# FAT42.net
KiCad netlist of a schematic drawn in Altium Designer
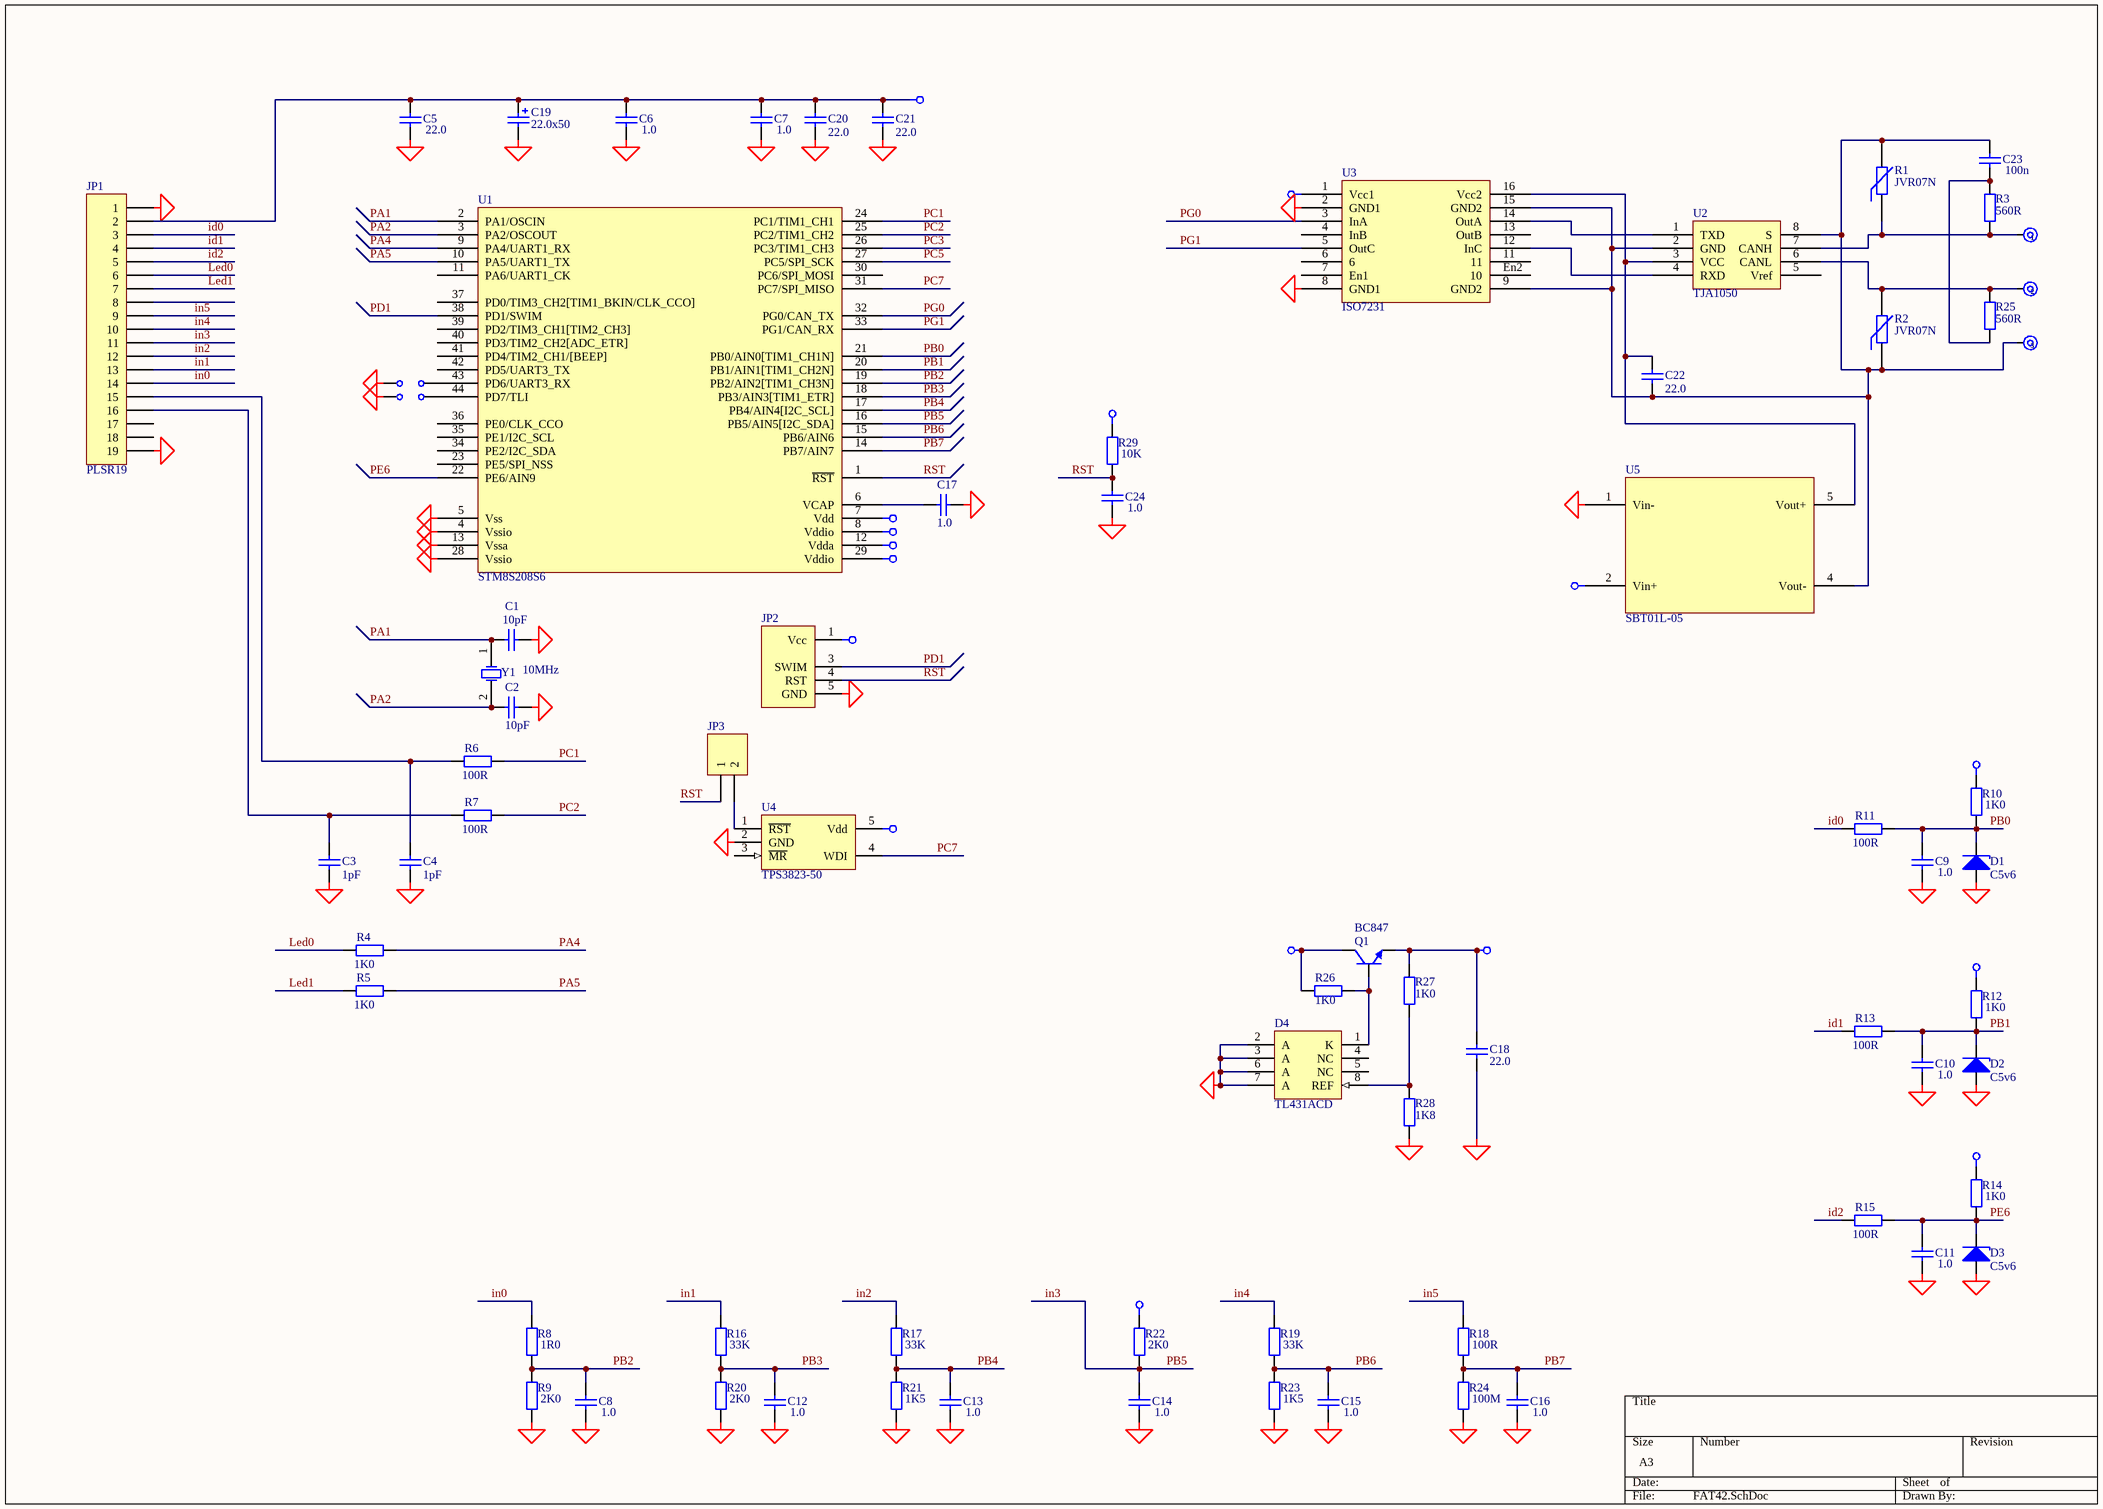
[diagram p0: FAT42.SchDoc]

(export (version "E")
  (design (tool "Eeschema 10.0.6"))
  (components
    (comp (ref "1")
      (value "~")
      (footprint "PIN2R")
      (description "Socket")
      (fields (field (name "MANUFACTURER") "Generic Components") (field (name "PUBLISHER") "Altium Limited"))
      (libsource (lib "PAL") (part "Socket_Ring"))
    )
    (comp (ref "2")
      (value "~")
      (footprint "PIN2R")
      (description "Socket")
      (fields (field (name "MANUFACTURER") "Generic Components") (field (name "PUBLISHER") "Altium Limited"))
      (libsource (lib "PAL") (part "Socket_Ring"))
    )
    (comp (ref "3")
      (value "~")
      (footprint "PIN2R")
      (description "Socket")
      (fields (field (name "MANUFACTURER") "Generic Components") (field (name "PUBLISHER") "Altium Limited"))
      (libsource (lib "PAL") (part "Socket_Ring"))
    )
    (comp (ref "C1")
      (value "10pF")
      (footprint "_1206")
      (description "Capacitor (Semiconductor SIM Model)")
      (fields (field (name "MANUFACTURER") "Generic Components") (field (name "PUBLISHER") "Altium Limited"))
      (libsource (lib "Miscellaneous Devices") (part "Cap Semi"))
    )
    (comp (ref "C2")
      (value "10pF")
      (footprint "_1206")
      (description "Capacitor (Semiconductor SIM Model)")
      (fields (field (name "MANUFACTURER") "Generic Components") (field (name "PUBLISHER") "Altium Limited"))
      (libsource (lib "Miscellaneous Devices") (part "Cap Semi"))
    )
    (comp (ref "C3")
      (value "1pF")
      (footprint "_1206")
      (description "Capacitor (Semiconductor SIM Model)")
      (fields (field (name "MANUFACTURER") "Generic Components") (field (name "PUBLISHER") "Altium Limited"))
      (libsource (lib "Miscellaneous Devices") (part "Cap Semi"))
    )
    (comp (ref "C4")
      (value "1pF")
      (footprint "_1206")
      (description "Capacitor (Semiconductor SIM Model)")
      (fields (field (name "MANUFACTURER") "Generic Components") (field (name "PUBLISHER") "Altium Limited"))
      (libsource (lib "Miscellaneous Devices") (part "Cap Semi"))
    )
    (comp (ref "C5")
      (value "22.0")
      (footprint "_1206")
      (description "Capacitor (Semiconductor SIM Model)")
      (fields (field (name "MANUFACTURER") "Generic Components") (field (name "PUBLISHER") "Altium Limited"))
      (libsource (lib "Miscellaneous Devices") (part "Cap Semi"))
    )
    (comp (ref "C6")
      (value "1.0")
      (footprint "_1206")
      (description "Capacitor (Semiconductor SIM Model)")
      (fields (field (name "MANUFACTURER") "Generic Components") (field (name "PUBLISHER") "Altium Limited"))
      (libsource (lib "Miscellaneous Devices") (part "Cap Semi"))
    )
    (comp (ref "C7")
      (value "1.0")
      (footprint "_1206")
      (description "Capacitor (Semiconductor SIM Model)")
      (fields (field (name "MANUFACTURER") "Generic Components") (field (name "PUBLISHER") "Altium Limited"))
      (libsource (lib "Miscellaneous Devices") (part "Cap Semi"))
    )
    (comp (ref "C8")
      (value "1.0")
      (footprint "_1206")
      (description "Capacitor (Semiconductor SIM Model)")
      (fields (field (name "MANUFACTURER") "Generic Components") (field (name "PUBLISHER") "Altium Limited"))
      (libsource (lib "Miscellaneous Devices") (part "Cap Semi"))
    )
    (comp (ref "C9")
      (value "1.0")
      (footprint "_1206")
      (description "Capacitor (Semiconductor SIM Model)")
      (fields (field (name "MANUFACTURER") "Generic Components") (field (name "PUBLISHER") "Altium Limited"))
      (libsource (lib "Miscellaneous Devices") (part "Cap Semi"))
    )
    (comp (ref "C10")
      (value "1.0")
      (footprint "_1206")
      (description "Capacitor (Semiconductor SIM Model)")
      (fields (field (name "MANUFACTURER") "Generic Components") (field (name "PUBLISHER") "Altium Limited"))
      (libsource (lib "Miscellaneous Devices") (part "Cap Semi"))
    )
    (comp (ref "C11")
      (value "1.0")
      (footprint "_1206")
      (description "Capacitor (Semiconductor SIM Model)")
      (fields (field (name "MANUFACTURER") "Generic Components") (field (name "PUBLISHER") "Altium Limited"))
      (libsource (lib "Miscellaneous Devices") (part "Cap Semi"))
    )
    (comp (ref "C12")
      (value "1.0")
      (footprint "_1206")
      (description "Capacitor (Semiconductor SIM Model)")
      (fields (field (name "MANUFACTURER") "Generic Components") (field (name "PUBLISHER") "Altium Limited"))
      (libsource (lib "Miscellaneous Devices") (part "Cap Semi"))
    )
    (comp (ref "C13")
      (value "1.0")
      (footprint "_1206")
      (description "Capacitor (Semiconductor SIM Model)")
      (fields (field (name "MANUFACTURER") "Generic Components") (field (name "PUBLISHER") "Altium Limited"))
      (libsource (lib "Miscellaneous Devices") (part "Cap Semi"))
    )
    (comp (ref "C14")
      (value "1.0")
      (footprint "_1206")
      (description "Capacitor (Semiconductor SIM Model)")
      (fields (field (name "MANUFACTURER") "Generic Components") (field (name "PUBLISHER") "Altium Limited"))
      (libsource (lib "Miscellaneous Devices") (part "Cap Semi"))
    )
    (comp (ref "C15")
      (value "1.0")
      (footprint "_1206")
      (description "Capacitor (Semiconductor SIM Model)")
      (fields (field (name "MANUFACTURER") "Generic Components") (field (name "PUBLISHER") "Altium Limited"))
      (libsource (lib "Miscellaneous Devices") (part "Cap Semi"))
    )
    (comp (ref "C16")
      (value "1.0")
      (footprint "_1206")
      (description "Capacitor (Semiconductor SIM Model)")
      (fields (field (name "MANUFACTURER") "Generic Components") (field (name "PUBLISHER") "Altium Limited"))
      (libsource (lib "Miscellaneous Devices") (part "Cap Semi"))
    )
    (comp (ref "C17")
      (value "1.0")
      (footprint "_1206")
      (description "Capacitor (Semiconductor SIM Model)")
      (fields (field (name "MANUFACTURER") "Generic Components") (field (name "PUBLISHER") "Altium Limited"))
      (libsource (lib "Miscellaneous Devices") (part "Cap Semi"))
    )
    (comp (ref "C18")
      (value "22.0")
      (footprint "_1206")
      (description "Capacitor (Semiconductor SIM Model)")
      (fields (field (name "MANUFACTURER") "Generic Components") (field (name "PUBLISHER") "Altium Limited"))
      (libsource (lib "Miscellaneous Devices") (part "Cap Semi"))
    )
    (comp (ref "C19")
      (value "22.0x50")
      (footprint "el3")
      (description "Polarized Capacitor (Radial)")
      (fields (field (name "MANUFACTURER") "Generic Components") (field (name "PUBLISHER") "Altium Limited"))
      (libsource (lib "PAL") (part "Cap Pol1"))
    )
    (comp (ref "C20")
      (value "22.0")
      (footprint "_1206")
      (description "Capacitor (Semiconductor SIM Model)")
      (fields (field (name "MANUFACTURER") "Generic Components") (field (name "PUBLISHER") "Altium Limited"))
      (libsource (lib "Miscellaneous Devices") (part "Cap Semi"))
    )
    (comp (ref "C21")
      (value "22.0")
      (footprint "_1206")
      (description "Capacitor (Semiconductor SIM Model)")
      (fields (field (name "MANUFACTURER") "Generic Components") (field (name "PUBLISHER") "Altium Limited"))
      (libsource (lib "Miscellaneous Devices") (part "Cap Semi"))
    )
    (comp (ref "C22")
      (value "22.0")
      (footprint "_1206")
      (description "Capacitor (Semiconductor SIM Model)")
      (fields (field (name "MANUFACTURER") "Generic Components") (field (name "PUBLISHER") "Altium Limited"))
      (libsource (lib "Miscellaneous Devices") (part "Cap Semi"))
    )
    (comp (ref "C23")
      (value "100n")
      (footprint "_1206")
      (description "Capacitor (Semiconductor SIM Model)")
      (fields (field (name "MANUFACTURER") "Generic Components") (field (name "PUBLISHER") "Altium Limited"))
      (libsource (lib "Miscellaneous Devices") (part "Cap Semi"))
    )
    (comp (ref "C24")
      (value "1.0")
      (footprint "_1206")
      (description "Capacitor (Semiconductor SIM Model)")
      (fields (field (name "MANUFACTURER") "Generic Components") (field (name "PUBLISHER") "Altium Limited"))
      (libsource (lib "Miscellaneous Devices") (part "Cap Semi"))
    )
    (comp (ref "D1")
      (value "C5v6")
      (footprint "_1206d")
      (description "Default Diode")
      (fields (field (name "MANUFACTURER") "Generic Components") (field (name "PUBLISHER") "Altium Limited"))
      (libsource (lib "PAL") (part "Zener"))
    )
    (comp (ref "D2")
      (value "C5v6")
      (footprint "_1206d")
      (description "Default Diode")
      (fields (field (name "MANUFACTURER") "Generic Components") (field (name "PUBLISHER") "Altium Limited"))
      (libsource (lib "PAL") (part "Zener"))
    )
    (comp (ref "D3")
      (value "C5v6")
      (footprint "_1206d")
      (description "Default Diode")
      (fields (field (name "MANUFACTURER") "Generic Components") (field (name "PUBLISHER") "Altium Limited"))
      (libsource (lib "PAL") (part "Zener"))
    )
    (comp (ref "D4")
      (value "TL431ACD")
      (footprint "SO-G8")
      (description "Programmable Precision Reference")
      (fields (field (name "MANUFACTURER") "Motorola") (field (name "PUBLISHER") "Altium Limited"))
      (libsource (lib "Motorola Power Management Voltage Reference") (part "TL431ACD"))
    )
    (comp (ref "J1")
      (value "~")
      (footprint "jmp")
      (description "Switch")
      (fields (field (name "MANUFACTURER") "Generic Components") (field (name "PUBLISHER") "Altium Limited"))
      (libsource (lib "PAL") (part "JMP"))
    )
    (comp (ref "J2")
      (value "~")
      (footprint "jmp")
      (description "Switch")
      (fields (field (name "MANUFACTURER") "Generic Components") (field (name "PUBLISHER") "Altium Limited"))
      (libsource (lib "PAL") (part "JMP"))
    )
    (comp (ref "JP1")
      (value "PLSR19")
      (footprint "HDR1X19")
      (description "Header, 19-Pin")
      (fields (field (name "MANUFACTURER") "Generic Components") (field (name "PUBLISHER") "Altium Limited"))
      (libsource (lib "Miscellaneous Connectors") (part "Header 19"))
    )
    (comp (ref "JP2") (value "~") (footprint "HDR1X5_uart") (libsource (lib "PAL") (part "SWIM_CONN")))
    (comp (ref "JP3")
      (value "PLS2")
      (footprint "HDR1X2")
      (description "Header, 2-Pin")
      (fields (field (name "MANUFACTURER") "Generic Components") (field (name "PUBLISHER") "Altium Limited"))
      (libsource (lib "Miscellaneous Connectors") (part "Header 2"))
    )
    (comp (ref "Q1")
      (value "BC847")
      (footprint "SO-G3")
      (description "General Purpose Transistor NPN Silicon")
      (fields (field (name "MANUFACTURER") "Motorola") (field (name "PUBLISHER") "Altium Limited"))
      (libsource (lib "PAL") (part "BC847ALT1"))
    )
    (comp (ref "R1")
      (value "JVR07N")
      (footprint "JVR07N")
      (description "Varistor (Voltage-Sensitive Resistor)")
      (fields (field (name "MANUFACTURER") "Generic Components") (field (name "PUBLISHER") "Altium Limited"))
      (libsource (lib "Miscellaneous Devices") (part "Res Varistor"))
    )
    (comp (ref "R2")
      (value "JVR07N")
      (footprint "JVR07N")
      (description "Varistor (Voltage-Sensitive Resistor)")
      (fields (field (name "MANUFACTURER") "Generic Components") (field (name "PUBLISHER") "Altium Limited"))
      (libsource (lib "Miscellaneous Devices") (part "Res Varistor"))
    )
    (comp (ref "R3")
      (value "560R")
      (footprint "_1206")
      (description "Resistor")
      (fields (field (name "MANUFACTURER") "Generic Components") (field (name "PUBLISHER") "Altium Limited"))
      (libsource (lib "") (part "Res2_1"))
    )
    (comp (ref "R4")
      (value "1K0")
      (footprint "_1206")
      (description "Resistor")
      (fields (field (name "MANUFACTURER") "Generic Components") (field (name "PUBLISHER") "Altium Limited"))
      (libsource (lib "") (part "Res2_1"))
    )
    (comp (ref "R5")
      (value "1K0")
      (footprint "_1206")
      (description "Resistor")
      (fields (field (name "MANUFACTURER") "Generic Components") (field (name "PUBLISHER") "Altium Limited"))
      (libsource (lib "") (part "Res2_1"))
    )
    (comp (ref "R6")
      (value "100R")
      (footprint "_1206")
      (description "Resistor")
      (fields (field (name "MANUFACTURER") "Generic Components") (field (name "PUBLISHER") "Altium Limited"))
      (libsource (lib "Miscellaneous Devices") (part "Res2"))
    )
    (comp (ref "R7")
      (value "100R")
      (footprint "_1206")
      (description "Resistor")
      (fields (field (name "MANUFACTURER") "Generic Components") (field (name "PUBLISHER") "Altium Limited"))
      (libsource (lib "Miscellaneous Devices") (part "Res2"))
    )
    (comp (ref "R8")
      (value "1R0")
      (footprint "_1206")
      (description "Resistor")
      (fields (field (name "MANUFACTURER") "Generic Components") (field (name "PUBLISHER") "Altium Limited"))
      (libsource (lib "") (part "Res2_2"))
    )
    (comp (ref "R9")
      (value "2K0")
      (footprint "_1206")
      (description "Resistor")
      (fields (field (name "MANUFACTURER") "Generic Components") (field (name "PUBLISHER") "Altium Limited"))
      (libsource (lib "") (part "Res2_2"))
    )
    (comp (ref "R10")
      (value "1K0")
      (footprint "_1206")
      (description "Resistor")
      (fields (field (name "MANUFACTURER") "Generic Components") (field (name "PUBLISHER") "Altium Limited"))
      (libsource (lib "") (part "Res2_3"))
    )
    (comp (ref "R11")
      (value "100R")
      (footprint "_1206")
      (description "Resistor")
      (fields (field (name "MANUFACTURER") "Generic Components") (field (name "PUBLISHER") "Altium Limited"))
      (libsource (lib "Miscellaneous Devices") (part "Res2"))
    )
    (comp (ref "R12")
      (value "1K0")
      (footprint "_1206")
      (description "Resistor")
      (fields (field (name "MANUFACTURER") "Generic Components") (field (name "PUBLISHER") "Altium Limited"))
      (libsource (lib "") (part "Res2_3"))
    )
    (comp (ref "R13")
      (value "100R")
      (footprint "_1206")
      (description "Resistor")
      (fields (field (name "MANUFACTURER") "Generic Components") (field (name "PUBLISHER") "Altium Limited"))
      (libsource (lib "Miscellaneous Devices") (part "Res2"))
    )
    (comp (ref "R14")
      (value "1K0")
      (footprint "_1206")
      (description "Resistor")
      (fields (field (name "MANUFACTURER") "Generic Components") (field (name "PUBLISHER") "Altium Limited"))
      (libsource (lib "") (part "Res2_3"))
    )
    (comp (ref "R15")
      (value "100R")
      (footprint "_1206")
      (description "Resistor")
      (fields (field (name "MANUFACTURER") "Generic Components") (field (name "PUBLISHER") "Altium Limited"))
      (libsource (lib "Miscellaneous Devices") (part "Res2"))
    )
    (comp (ref "R16")
      (value "33K")
      (footprint "_1206")
      (description "Resistor")
      (fields (field (name "MANUFACTURER") "Generic Components") (field (name "PUBLISHER") "Altium Limited"))
      (libsource (lib "") (part "Res2_2"))
    )
    (comp (ref "R17")
      (value "33K")
      (footprint "_1206")
      (description "Resistor")
      (fields (field (name "MANUFACTURER") "Generic Components") (field (name "PUBLISHER") "Altium Limited"))
      (libsource (lib "") (part "Res2_2"))
    )
    (comp (ref "R18")
      (value "100R")
      (footprint "_1206")
      (description "Resistor")
      (fields (field (name "MANUFACTURER") "Generic Components") (field (name "PUBLISHER") "Altium Limited"))
      (libsource (lib "") (part "Res2_2"))
    )
    (comp (ref "R19")
      (value "33K")
      (footprint "_1206")
      (description "Resistor")
      (fields (field (name "MANUFACTURER") "Generic Components") (field (name "PUBLISHER") "Altium Limited"))
      (libsource (lib "") (part "Res2_2"))
    )
    (comp (ref "R20")
      (value "2K0")
      (footprint "_1206")
      (description "Resistor")
      (fields (field (name "MANUFACTURER") "Generic Components") (field (name "PUBLISHER") "Altium Limited"))
      (libsource (lib "") (part "Res2_2"))
    )
    (comp (ref "R21")
      (value "1K5")
      (footprint "_1206")
      (description "Resistor")
      (fields (field (name "MANUFACTURER") "Generic Components") (field (name "PUBLISHER") "Altium Limited"))
      (libsource (lib "") (part "Res2_2"))
    )
    (comp (ref "R22")
      (value "2K0")
      (footprint "_1206")
      (description "Resistor")
      (fields (field (name "MANUFACTURER") "Generic Components") (field (name "PUBLISHER") "Altium Limited"))
      (libsource (lib "") (part "Res2_2"))
    )
    (comp (ref "R23")
      (value "1K5")
      (footprint "_1206")
      (description "Resistor")
      (fields (field (name "MANUFACTURER") "Generic Components") (field (name "PUBLISHER") "Altium Limited"))
      (libsource (lib "") (part "Res2_2"))
    )
    (comp (ref "R24")
      (value "100M")
      (footprint "_1206")
      (description "Resistor")
      (fields (field (name "MANUFACTURER") "Generic Components") (field (name "PUBLISHER") "Altium Limited"))
      (libsource (lib "") (part "Res2_2"))
    )
    (comp (ref "R25")
      (value "560R")
      (footprint "_1206")
      (description "Resistor")
      (fields (field (name "MANUFACTURER") "Generic Components") (field (name "PUBLISHER") "Altium Limited"))
      (libsource (lib "") (part "Res2_1"))
    )
    (comp (ref "R26")
      (value "1K0")
      (footprint "_1206")
      (description "Resistor")
      (fields (field (name "MANUFACTURER") "Generic Components") (field (name "PUBLISHER") "Altium Limited"))
      (libsource (lib "") (part "Res2_4"))
    )
    (comp (ref "R27")
      (value "1K0")
      (footprint "_1206")
      (description "Resistor")
      (fields (field (name "MANUFACTURER") "Generic Components") (field (name "PUBLISHER") "Altium Limited"))
      (libsource (lib "") (part "Res2_1"))
    )
    (comp (ref "R28")
      (value "1K8")
      (footprint "_1206")
      (description "Resistor")
      (fields (field (name "MANUFACTURER") "Generic Components") (field (name "PUBLISHER") "Altium Limited"))
      (libsource (lib "") (part "Res2_1"))
    )
    (comp (ref "R29")
      (value "10K")
      (footprint "_1206")
      (description "Resistor")
      (fields (field (name "MANUFACTURER") "Generic Components") (field (name "PUBLISHER") "Altium Limited"))
      (libsource (lib "") (part "Res2_3"))
    )
    (comp (ref "U1")
      (value "STM8S208S6")
      (footprint "QFP10X10-G44/G10N")
      (libsource (lib "PAL") (part "STM8S208S6"))
    )
    (comp (ref "U2") (value "TJA1050") (footprint "SO-G8/D5") (libsource (lib "PAL") (part "TJA1050")))
    (comp (ref "U3") (value "ISO7231") (footprint "SO-G16/D10.4") (libsource (lib "PAL") (part "ISO7231")))
    (comp (ref "U4")
      (value "TPS3823-50")
      (footprint "SO-G5/P.95")
      (description "Reset IC")
      (fields
        (field (name "MANUFACTURER") "National Semiconductor")
        (field (name "PUBLISHER") "Altium Limited")
      )
      (libsource (lib "PAL") (part "TPS3823"))
    )
    (comp (ref "U5") (value "SBT01L-05") (footprint "SBT01DET01") (libsource (lib "PAL") (part "SBT01L")))
    (comp (ref "Y1")
      (value "10MHz")
      (footprint "QWARZ1")
      (description "Crystal Oscillator")
      (fields (field (name "MANUFACTURER") "Generic Components") (field (name "PUBLISHER") "Altium Limited"))
      (libsource (lib "Miscellaneous Devices") (part "XTAL"))
    )
  )
  (nets
    (net (code "1") (name "+5v") (class "Default")
      (node (ref "C19") (pin "1") (pinfunction "1_1") (pintype "passive"))
      (node (ref "C20") (pin "1") (pinfunction "1_1") (pintype "passive"))
      (node (ref "C21") (pin "1") (pinfunction "1_1") (pintype "passive"))
      (node (ref "C5") (pin "2") (pinfunction "2_2") (pintype "passive"))
      (node (ref "C6") (pin "2") (pinfunction "2_2") (pintype "passive"))
      (node (ref "C7") (pin "2") (pinfunction "2_2") (pintype "passive"))
      (node (ref "JP1") (pin "2") (pinfunction "2_2") (pintype "passive"))
      (node (ref "JP2") (pin "1") (pinfunction "Vcc_1") (pintype "passive"))
      (node (ref "Q1") (pin "3") (pinfunction "C_3") (pintype "passive"))
      (node (ref "R10") (pin "1") (pinfunction "1_1") (pintype "passive"))
      (node (ref "R12") (pin "1") (pinfunction "1_1") (pintype "passive"))
      (node (ref "R14") (pin "1") (pinfunction "1_1") (pintype "passive"))
      (node (ref "R22") (pin "2") (pinfunction "2_2") (pintype "passive"))
      (node (ref "R26") (pin "1") (pinfunction "1_1") (pintype "passive"))
      (node (ref "R29") (pin "1") (pinfunction "1_1") (pintype "passive"))
      (node (ref "U1") (pin "29") (pinfunction "Vddio_29") (pintype "passive"))
      (node (ref "U1") (pin "7") (pinfunction "Vdd_7") (pintype "passive"))
      (node (ref "U1") (pin "8") (pinfunction "Vddio_8") (pintype "passive"))
      (node (ref "U3") (pin "1") (pinfunction "Vcc1_1") (pintype "passive"))
      (node (ref "U4") (pin "5") (pinfunction "Vdd_5") (pintype "power_in"))
      (node (ref "U5") (pin "2") (pinfunction "Vin+_2") (pintype "passive"))
    )
    (net (code "2") (name "/Led0") (class "Default")
      (node (ref "JP1") (pin "6") (pinfunction "6_6") (pintype "passive"))
      (node (ref "R4") (pin "1") (pinfunction "1_1") (pintype "passive"))
    )
    (net (code "3") (name "/Led1") (class "Default")
      (node (ref "JP1") (pin "7") (pinfunction "7_7") (pintype "passive"))
      (node (ref "R5") (pin "1") (pinfunction "1_1") (pintype "passive"))
    )
    (net (code "4") (name "/PA1") (class "Default")
      (node (ref "C1") (pin "2") (pinfunction "2_2") (pintype "passive"))
      (node (ref "U1") (pin "2") (pinfunction "PA1/OSCIN_2") (pintype "passive"))
      (node (ref "Y1") (pin "1") (pinfunction "OSC1_1") (pintype "passive"))
    )
    (net (code "5") (name "/PA2") (class "Default")
      (node (ref "C2") (pin "2") (pinfunction "2_2") (pintype "passive"))
      (node (ref "U1") (pin "3") (pinfunction "PA2/OSCOUT_3") (pintype "passive"))
      (node (ref "Y1") (pin "2") (pinfunction "OSC2_2") (pintype "passive"))
    )
    (net (code "6") (name "/PA4") (class "Default")
      (node (ref "R4") (pin "2") (pinfunction "2_2") (pintype "passive"))
      (node (ref "U1") (pin "9") (pinfunction "PA4/UART1_RX_9") (pintype "passive"))
    )
    (net (code "7") (name "/PA5") (class "Default")
      (node (ref "R5") (pin "2") (pinfunction "2_2") (pintype "passive"))
      (node (ref "U1") (pin "10") (pinfunction "PA5/UART1_TX_10") (pintype "passive"))
    )
    (net (code "8") (name "/PB0") (class "Default")
      (node (ref "C9") (pin "2") (pinfunction "2_2") (pintype "passive"))
      (node (ref "D1") (pin "2") (pinfunction "K_2") (pintype "passive"))
      (node (ref "R10") (pin "2") (pinfunction "2_2") (pintype "passive"))
      (node (ref "R11") (pin "1") (pinfunction "1_1") (pintype "passive"))
      (node (ref "U1") (pin "21") (pinfunction "PB0/AIN0[TIM1_CH1N]_21") (pintype "passive"))
    )
    (net (code "9") (name "/PB1") (class "Default")
      (node (ref "C10") (pin "2") (pinfunction "2_2") (pintype "passive"))
      (node (ref "D2") (pin "2") (pinfunction "K_2") (pintype "passive"))
      (node (ref "R12") (pin "2") (pinfunction "2_2") (pintype "passive"))
      (node (ref "R13") (pin "1") (pinfunction "1_1") (pintype "passive"))
      (node (ref "U1") (pin "20") (pinfunction "PB1/AIN1[TIM1_CH2N]_20") (pintype "passive"))
    )
    (net (code "10") (name "/PB2") (class "Default")
      (node (ref "C8") (pin "2") (pinfunction "2_2") (pintype "passive"))
      (node (ref "R8") (pin "1") (pinfunction "1_1") (pintype "passive"))
      (node (ref "R9") (pin "2") (pinfunction "2_2") (pintype "passive"))
      (node (ref "U1") (pin "19") (pinfunction "PB2/AIN2[TIM1_CH3N]_19") (pintype "passive"))
    )
    (net (code "11") (name "/PB3") (class "Default")
      (node (ref "C12") (pin "2") (pinfunction "2_2") (pintype "passive"))
      (node (ref "R16") (pin "1") (pinfunction "1_1") (pintype "passive"))
      (node (ref "R20") (pin "2") (pinfunction "2_2") (pintype "passive"))
      (node (ref "U1") (pin "18") (pinfunction "PB3/AIN3[TIM1_ETR]_18") (pintype "passive"))
    )
    (net (code "12") (name "/PB4") (class "Default")
      (node (ref "C13") (pin "2") (pinfunction "2_2") (pintype "passive"))
      (node (ref "R17") (pin "1") (pinfunction "1_1") (pintype "passive"))
      (node (ref "R21") (pin "2") (pinfunction "2_2") (pintype "passive"))
      (node (ref "U1") (pin "17") (pinfunction "PB4/AIN4[I2C_SCL]_17") (pintype "passive"))
    )
    (net (code "13") (name "/PB5") (class "Default")
      (node (ref "C14") (pin "2") (pinfunction "2_2") (pintype "passive"))
      (node (ref "JP1") (pin "11") (pinfunction "11_11") (pintype "passive"))
      (node (ref "R22") (pin "1") (pinfunction "1_1") (pintype "passive"))
      (node (ref "U1") (pin "16") (pinfunction "PB5/AIN5[I2C_SDA]_16") (pintype "passive"))
    )
    (net (code "14") (name "/PB6") (class "Default")
      (node (ref "C15") (pin "2") (pinfunction "2_2") (pintype "passive"))
      (node (ref "R19") (pin "1") (pinfunction "1_1") (pintype "passive"))
      (node (ref "R23") (pin "2") (pinfunction "2_2") (pintype "passive"))
      (node (ref "U1") (pin "15") (pinfunction "PB6/AIN6_15") (pintype "passive"))
    )
    (net (code "15") (name "/PB7") (class "Default")
      (node (ref "C16") (pin "2") (pinfunction "2_2") (pintype "passive"))
      (node (ref "R18") (pin "1") (pinfunction "1_1") (pintype "passive"))
      (node (ref "R24") (pin "2") (pinfunction "2_2") (pintype "passive"))
      (node (ref "U1") (pin "14") (pinfunction "PB7/AIN7_14") (pintype "passive"))
    )
    (net (code "16") (name "/PC1") (class "Default")
      (node (ref "R6") (pin "1") (pinfunction "1_1") (pintype "passive"))
      (node (ref "U1") (pin "24") (pinfunction "PC1/TIM1_CH1_24") (pintype "passive"))
    )
    (net (code "17") (name "/PC2") (class "Default")
      (node (ref "R7") (pin "1") (pinfunction "1_1") (pintype "passive"))
      (node (ref "U1") (pin "25") (pinfunction "PC2/TIM1_CH2_25") (pintype "passive"))
    )
    (net (code "18") (name "/PC3") (class "Default")
      (node (ref "U1") (pin "26") (pinfunction "PC3/TIM1_CH3_26") (pintype "passive"))
    )
    (net (code "19") (name "/PC5") (class "Default")
      (node (ref "U1") (pin "27") (pinfunction "PC5/SPI_SCK_27") (pintype "passive"))
    )
    (net (code "20") (name "/PC7") (class "Default")
      (node (ref "U1") (pin "31") (pinfunction "PC7/SPI_MISO_31") (pintype "passive"))
      (node (ref "U4") (pin "4") (pinfunction "WDI_4") (pintype "passive"))
    )
    (net (code "21") (name "/PD1") (class "Default")
      (node (ref "JP2") (pin "3") (pinfunction "SWIM_3") (pintype "passive"))
      (node (ref "U1") (pin "38") (pinfunction "PD1/SWIM_38") (pintype "passive"))
    )
    (net (code "22") (name "/PE6") (class "Default")
      (node (ref "C11") (pin "2") (pinfunction "2_2") (pintype "passive"))
      (node (ref "D3") (pin "2") (pinfunction "K_2") (pintype "passive"))
      (node (ref "R14") (pin "2") (pinfunction "2_2") (pintype "passive"))
      (node (ref "R15") (pin "1") (pinfunction "1_1") (pintype "passive"))
      (node (ref "U1") (pin "22") (pinfunction "PE6/AIN9_22") (pintype "passive"))
    )
    (net (code "23") (name "/PG0") (class "Default")
      (node (ref "U1") (pin "32") (pinfunction "PG0/CAN_TX_32") (pintype "passive"))
      (node (ref "U3") (pin "3") (pinfunction "InA_3") (pintype "passive"))
    )
    (net (code "24") (name "/PG1") (class "Default")
      (node (ref "U1") (pin "33") (pinfunction "PG1/CAN_RX_33") (pintype "passive"))
      (node (ref "U3") (pin "5") (pinfunction "OutC_5") (pintype "passive"))
    )
    (net (code "25") (name "/RST") (class "Default")
      (node (ref "C24") (pin "2") (pinfunction "2_2") (pintype "passive"))
      (node (ref "JP2") (pin "4") (pinfunction "RST_4") (pintype "passive"))
      (node (ref "JP3") (pin "1") (pinfunction "1_1") (pintype "passive"))
      (node (ref "R29") (pin "2") (pinfunction "2_2") (pintype "passive"))
      (node (ref "U1") (pin "1") (pinfunction "~{RST}_1") (pintype "passive"))
    )
    (net (code "26") (name "/id0") (class "Default")
      (node (ref "JP1") (pin "3") (pinfunction "3_3") (pintype "passive"))
      (node (ref "R11") (pin "2") (pinfunction "2_2") (pintype "passive"))
    )
    (net (code "27") (name "/id1") (class "Default")
      (node (ref "JP1") (pin "4") (pinfunction "4_4") (pintype "passive"))
      (node (ref "R13") (pin "2") (pinfunction "2_2") (pintype "passive"))
    )
    (net (code "28") (name "/id2") (class "Default")
      (node (ref "JP1") (pin "5") (pinfunction "5_5") (pintype "passive"))
      (node (ref "R15") (pin "2") (pinfunction "2_2") (pintype "passive"))
    )
    (net (code "29") (name "/in0") (class "Default")
      (node (ref "JP1") (pin "14") (pinfunction "14_14") (pintype "passive"))
      (node (ref "R8") (pin "2") (pinfunction "2_2") (pintype "passive"))
    )
    (net (code "30") (name "/in1") (class "Default")
      (node (ref "JP1") (pin "13") (pinfunction "13_13") (pintype "passive"))
      (node (ref "R16") (pin "2") (pinfunction "2_2") (pintype "passive"))
    )
    (net (code "31") (name "/in2") (class "Default")
      (node (ref "JP1") (pin "12") (pinfunction "12_12") (pintype "passive"))
      (node (ref "R17") (pin "2") (pinfunction "2_2") (pintype "passive"))
    )
    (net (code "32") (name "/in4") (class "Default")
      (node (ref "JP1") (pin "10") (pinfunction "10_10") (pintype "passive"))
      (node (ref "R19") (pin "2") (pinfunction "2_2") (pintype "passive"))
    )
    (net (code "33") (name "/in5") (class "Default")
      (node (ref "JP1") (pin "9") (pinfunction "9_9") (pintype "passive"))
      (node (ref "R18") (pin "2") (pinfunction "2_2") (pintype "passive"))
    )
    (net (code "34") (name "GND") (class "Default")
      (node (ref "C1") (pin "1") (pinfunction "1_1") (pintype "passive"))
      (node (ref "C10") (pin "1") (pinfunction "1_1") (pintype "passive"))
      (node (ref "C11") (pin "1") (pinfunction "1_1") (pintype "passive"))
      (node (ref "C12") (pin "1") (pinfunction "1_1") (pintype "passive"))
      (node (ref "C13") (pin "1") (pinfunction "1_1") (pintype "passive"))
      (node (ref "C14") (pin "1") (pinfunction "1_1") (pintype "passive"))
      (node (ref "C15") (pin "1") (pinfunction "1_1") (pintype "passive"))
      (node (ref "C16") (pin "1") (pinfunction "1_1") (pintype "passive"))
      (node (ref "C17") (pin "1") (pinfunction "1_1") (pintype "passive"))
      (node (ref "C18") (pin "1") (pinfunction "1_1") (pintype "passive"))
      (node (ref "C19") (pin "2") (pinfunction "2_2") (pintype "passive"))
      (node (ref "C2") (pin "1") (pinfunction "1_1") (pintype "passive"))
      (node (ref "C20") (pin "2") (pinfunction "2_2") (pintype "passive"))
      (node (ref "C21") (pin "2") (pinfunction "2_2") (pintype "passive"))
      (node (ref "C24") (pin "1") (pinfunction "1_1") (pintype "passive"))
      (node (ref "C3") (pin "1") (pinfunction "1_1") (pintype "passive"))
      (node (ref "C4") (pin "1") (pinfunction "1_1") (pintype "passive"))
      (node (ref "C5") (pin "1") (pinfunction "1_1") (pintype "passive"))
      (node (ref "C6") (pin "1") (pinfunction "1_1") (pintype "passive"))
      (node (ref "C7") (pin "1") (pinfunction "1_1") (pintype "passive"))
      (node (ref "C8") (pin "1") (pinfunction "1_1") (pintype "passive"))
      (node (ref "C9") (pin "1") (pinfunction "1_1") (pintype "passive"))
      (node (ref "D1") (pin "1") (pinfunction "A_1") (pintype "passive"))
      (node (ref "D2") (pin "1") (pinfunction "A_1") (pintype "passive"))
      (node (ref "D3") (pin "1") (pinfunction "A_1") (pintype "passive"))
      (node (ref "D4") (pin "2") (pinfunction "A_2") (pintype "passive"))
      (node (ref "D4") (pin "3") (pinfunction "A_3") (pintype "passive"))
      (node (ref "D4") (pin "6") (pinfunction "A_6") (pintype "passive"))
      (node (ref "D4") (pin "7") (pinfunction "A_7") (pintype "passive"))
      (node (ref "J1") (pin "1") (pinfunction "1_1") (pintype "passive"))
      (node (ref "J2") (pin "1") (pinfunction "1_1") (pintype "passive"))
      (node (ref "JP1") (pin "1") (pinfunction "1_1") (pintype "passive"))
      (node (ref "JP1") (pin "19") (pinfunction "19_19") (pintype "passive"))
      (node (ref "JP2") (pin "5") (pinfunction "GND_5") (pintype "passive"))
      (node (ref "R20") (pin "1") (pinfunction "1_1") (pintype "passive"))
      (node (ref "R21") (pin "1") (pinfunction "1_1") (pintype "passive"))
      (node (ref "R23") (pin "1") (pinfunction "1_1") (pintype "passive"))
      (node (ref "R24") (pin "1") (pinfunction "1_1") (pintype "passive"))
      (node (ref "R28") (pin "1") (pinfunction "1_1") (pintype "passive"))
      (node (ref "R9") (pin "1") (pinfunction "1_1") (pintype "passive"))
      (node (ref "U1") (pin "13") (pinfunction "Vssa_13") (pintype "passive"))
      (node (ref "U1") (pin "28") (pinfunction "Vssio_28") (pintype "passive"))
      (node (ref "U1") (pin "4") (pinfunction "Vssio_4") (pintype "passive"))
      (node (ref "U1") (pin "5") (pinfunction "Vss_5") (pintype "passive"))
      (node (ref "U3") (pin "2") (pinfunction "GND1_2") (pintype "passive"))
      (node (ref "U3") (pin "8") (pinfunction "GND1_8") (pintype "passive"))
      (node (ref "U4") (pin "2") (pinfunction "GND_2") (pintype "power_in"))
      (node (ref "U5") (pin "1") (pinfunction "Vin-_1") (pintype "passive"))
    )
    (net (code "35") (name "Net-(C3-Pad2)") (class "Default")
      (node (ref "C3") (pin "2") (pinfunction "2_2") (pintype "passive"))
      (node (ref "JP1") (pin "16") (pinfunction "16_16") (pintype "passive"))
      (node (ref "R7") (pin "2") (pinfunction "2_2") (pintype "passive"))
    )
    (net (code "36") (name "Net-(C4-Pad2)") (class "Default")
      (node (ref "C4") (pin "2") (pinfunction "2_2") (pintype "passive"))
      (node (ref "JP1") (pin "15") (pinfunction "15_15") (pintype "passive"))
      (node (ref "R6") (pin "2") (pinfunction "2_2") (pintype "passive"))
    )
    (net (code "37") (name "Net-(C23-Pad1)") (class "Default")
      (node (ref "C23") (pin "1") (pinfunction "1_1") (pintype "passive"))
      (node (ref "R25") (pin "1") (pinfunction "1_1") (pintype "passive"))
      (node (ref "R3") (pin "2") (pinfunction "2_2") (pintype "passive"))
    )
    (net (code "38") (name "Net-(D4-K)") (class "Default")
      (node (ref "D4") (pin "1") (pinfunction "K_1") (pintype "passive"))
      (node (ref "Q1") (pin "1") (pinfunction "B_1") (pintype "passive"))
      (node (ref "R26") (pin "2") (pinfunction "2_2") (pintype "passive"))
    )
    (net (code "39") (name "Net-(D4-REF)") (class "Default")
      (node (ref "D4") (pin "8") (pinfunction "REF_8") (pintype "input"))
      (node (ref "R27") (pin "1") (pinfunction "1_1") (pintype "passive"))
      (node (ref "R28") (pin "2") (pinfunction "2_2") (pintype "passive"))
    )
    (net (code "40") (name "Net-(U1-PD6{slash}UART3_RX)") (class "Default")
      (node (ref "J1") (pin "2") (pinfunction "2_2") (pintype "passive"))
      (node (ref "U1") (pin "43") (pinfunction "PD6/UART3_RX_43") (pintype "passive"))
    )
    (net (code "41") (name "Net-(U1-PD7{slash}TLI)") (class "Default")
      (node (ref "J2") (pin "2") (pinfunction "2_2") (pintype "passive"))
      (node (ref "U1") (pin "44") (pinfunction "PD7/TLI_44") (pintype "passive"))
    )
    (net (code "42") (name "Net-(U1-VCAP)") (class "Default")
      (node (ref "C17") (pin "2") (pinfunction "2_2") (pintype "passive"))
      (node (ref "U1") (pin "6") (pinfunction "VCAP_6") (pintype "passive"))
    )
    (net (code "43") (name "Net-(U2-CANH)") (class "Default")
      (node (ref "1") (pin "1") (pinfunction "1_1") (pintype "passive"))
      (node (ref "R1") (pin "1") (pinfunction "1_1") (pintype "passive"))
      (node (ref "R3") (pin "1") (pinfunction "1_1") (pintype "passive"))
      (node (ref "U2") (pin "7") (pinfunction "CANH_7") (pintype "passive"))
    )
    (net (code "44") (name "Net-(U2-CANL)") (class "Default")
      (node (ref "2") (pin "1") (pinfunction "1_1") (pintype "passive"))
      (node (ref "R2") (pin "2") (pinfunction "2_2") (pintype "passive"))
      (node (ref "R25") (pin "2") (pinfunction "2_2") (pintype "passive"))
      (node (ref "U2") (pin "6") (pinfunction "CANL_6") (pintype "passive"))
    )
    (net (code "45") (name "Net-(U2-GND)") (class "Default")
      (node (ref "3") (pin "1") (pinfunction "1_1") (pintype "passive"))
      (node (ref "C22") (pin "2") (pinfunction "2_2") (pintype "passive"))
      (node (ref "C23") (pin "2") (pinfunction "2_2") (pintype "passive"))
      (node (ref "R1") (pin "2") (pinfunction "2_2") (pintype "passive"))
      (node (ref "R2") (pin "1") (pinfunction "1_1") (pintype "passive"))
      (node (ref "U2") (pin "2") (pinfunction "GND_2") (pintype "passive"))
      (node (ref "U2") (pin "8") (pinfunction "S_8") (pintype "passive"))
      (node (ref "U3") (pin "15") (pinfunction "GND2_15") (pintype "passive"))
      (node (ref "U3") (pin "9") (pinfunction "GND2_9") (pintype "passive"))
      (node (ref "U5") (pin "4") (pinfunction "Vout-_4") (pintype "passive"))
    )
    (net (code "46") (name "Net-(U2-RXD)") (class "Default")
      (node (ref "U2") (pin "4") (pinfunction "RXD_4") (pintype "passive"))
      (node (ref "U3") (pin "12") (pinfunction "InC_12") (pintype "passive"))
    )
    (net (code "47") (name "Net-(U2-TXD)") (class "Default")
      (node (ref "U2") (pin "1") (pinfunction "TXD_1") (pintype "passive"))
      (node (ref "U3") (pin "14") (pinfunction "OutA_14") (pintype "passive"))
    )
    (net (code "48") (name "Net-(U2-VCC)") (class "Default")
      (node (ref "C22") (pin "1") (pinfunction "1_1") (pintype "passive"))
      (node (ref "U2") (pin "3") (pinfunction "VCC_3") (pintype "passive"))
      (node (ref "U3") (pin "16") (pinfunction "Vcc2_16") (pintype "passive"))
      (node (ref "U5") (pin "5") (pinfunction "Vout+_5") (pintype "passive"))
    )
    (net (code "49") (name "Net-(U4-~{RST})") (class "Default")
      (node (ref "JP3") (pin "2") (pinfunction "2_2") (pintype "passive"))
      (node (ref "U4") (pin "1") (pinfunction "~{RST}_1") (pintype "power_in"))
    )
    (net (code "50") (name "Uref") (class "Default")
      (node (ref "C18") (pin "2") (pinfunction "2_2") (pintype "passive"))
      (node (ref "Q1") (pin "2") (pinfunction "E_2") (pintype "passive"))
      (node (ref "R27") (pin "2") (pinfunction "2_2") (pintype "passive"))
      (node (ref "U1") (pin "12") (pinfunction "Vdda_12") (pintype "passive"))
    )
    (net (code "51") (name "unconnected-(D4-NC-Pad4)") (class "Default")
      (node (ref "D4") (pin "4") (pinfunction "NC_4") (pintype "passive"))
    )
    (net (code "52") (name "unconnected-(D4-NC-Pad5)") (class "Default")
      (node (ref "D4") (pin "5") (pinfunction "NC_5") (pintype "passive"))
    )
    (net (code "53") (name "unconnected-(JP1-Pad8)") (class "Default")
      (node (ref "JP1") (pin "8") (pinfunction "8_8") (pintype "passive"))
    )
    (net (code "54") (name "unconnected-(JP1-Pad17)") (class "Default")
      (node (ref "JP1") (pin "17") (pinfunction "17_17") (pintype "passive"))
    )
    (net (code "55") (name "unconnected-(JP1-Pad18)") (class "Default")
      (node (ref "JP1") (pin "18") (pinfunction "18_18") (pintype "passive"))
    )
    (net (code "56") (name "unconnected-(U1-PA6{slash}UART1_CK-Pad11)") (class "Default")
      (node (ref "U1") (pin "11") (pinfunction "PA6/UART1_CK_11") (pintype "passive"))
    )
    (net (code "57") (name "unconnected-(U1-PC6{slash}SPI_MOSI-Pad30)") (class "Default")
      (node (ref "U1") (pin "30") (pinfunction "PC6/SPI_MOSI_30") (pintype "passive"))
    )
    (net (code "58") (name "unconnected-(U1-PD0{slash}TIM3_CH2[TIM1_BKIN{slash}CLK_CCO]-Pad37)") (class "Default")
      (node (ref "U1") (pin "37") (pinfunction "PD0/TIM3_CH2[TIM1_BKIN/CLK_CCO]_37") (pintype "passive"))
    )
    (net (code "59") (name "unconnected-(U1-PD2{slash}TIM3_CH1[TIM2_CH3]-Pad39)") (class "Default")
      (node (ref "U1") (pin "39") (pinfunction "PD2/TIM3_CH1[TIM2_CH3]_39") (pintype "passive"))
    )
    (net (code "60") (name "unconnected-(U1-PD3{slash}TIM2_CH2[ADC_ETR]-Pad40)") (class "Default")
      (node (ref "U1") (pin "40") (pinfunction "PD3/TIM2_CH2[ADC_ETR]_40") (pintype "passive"))
    )
    (net (code "61") (name "unconnected-(U1-PD4{slash}TIM2_CH1{slash}[BEEP]-Pad41)") (class "Default")
      (node (ref "U1") (pin "41") (pinfunction "PD4/TIM2_CH1/[BEEP]_41") (pintype "passive"))
    )
    (net (code "62") (name "unconnected-(U1-PD5{slash}UART3_TX-Pad42)") (class "Default")
      (node (ref "U1") (pin "42") (pinfunction "PD5/UART3_TX_42") (pintype "passive"))
    )
    (net (code "63") (name "unconnected-(U1-PE0{slash}CLK_CCO-Pad36)") (class "Default")
      (node (ref "U1") (pin "36") (pinfunction "PE0/CLK_CCO_36") (pintype "passive"))
    )
    (net (code "64") (name "unconnected-(U1-PE1{slash}I2C_SCL-Pad35)") (class "Default")
      (node (ref "U1") (pin "35") (pinfunction "PE1/I2C_SCL_35") (pintype "passive"))
    )
    (net (code "65") (name "unconnected-(U1-PE2{slash}I2C_SDA-Pad34)") (class "Default")
      (node (ref "U1") (pin "34") (pinfunction "PE2/I2C_SDA_34") (pintype "passive"))
    )
    (net (code "66") (name "unconnected-(U1-PE5{slash}SPI_NSS-Pad23)") (class "Default")
      (node (ref "U1") (pin "23") (pinfunction "PE5/SPI_NSS_23") (pintype "passive"))
    )
    (net (code "67") (name "unconnected-(U2-Vref-Pad5)") (class "Default")
      (node (ref "U2") (pin "5") (pinfunction "Vref_5") (pintype "passive"))
    )
    (net (code "68") (name "unconnected-(U3-10-PadEn2)") (class "Default")
      (node (ref "U3") (pin "En2") (pinfunction "10_En2") (pintype "passive"))
    )
    (net (code "69") (name "unconnected-(U3-En1-Pad7)") (class "Default")
      (node (ref "U3") (pin "7") (pinfunction "En1_7") (pintype "passive"))
    )
    (net (code "70") (name "unconnected-(U3-InB-Pad4)") (class "Default")
      (node (ref "U3") (pin "4") (pinfunction "InB_4") (pintype "passive"))
    )
    (net (code "71") (name "unconnected-(U3-OutB-Pad13)") (class "Default")
      (node (ref "U3") (pin "13") (pinfunction "OutB_13") (pintype "passive"))
    )
    (net (code "72") (name "unconnected-(U3-Pad6)") (class "Default")
      (node (ref "U3") (pin "6") (pinfunction "6_6") (pintype "passive"))
    )
    (net (code "73") (name "unconnected-(U3-Pad11)") (class "Default")
      (node (ref "U3") (pin "11") (pinfunction "11_11") (pintype "passive"))
    )
    (net (code "74") (name "unconnected-(U4-~{MR}-Pad3)") (class "Default")
      (node (ref "U4") (pin "3") (pinfunction "~{MR}_3") (pintype "input"))
    )
  )
)
